# GridInverter.net
KiCad netlist of a schematic drawn in EAGLE
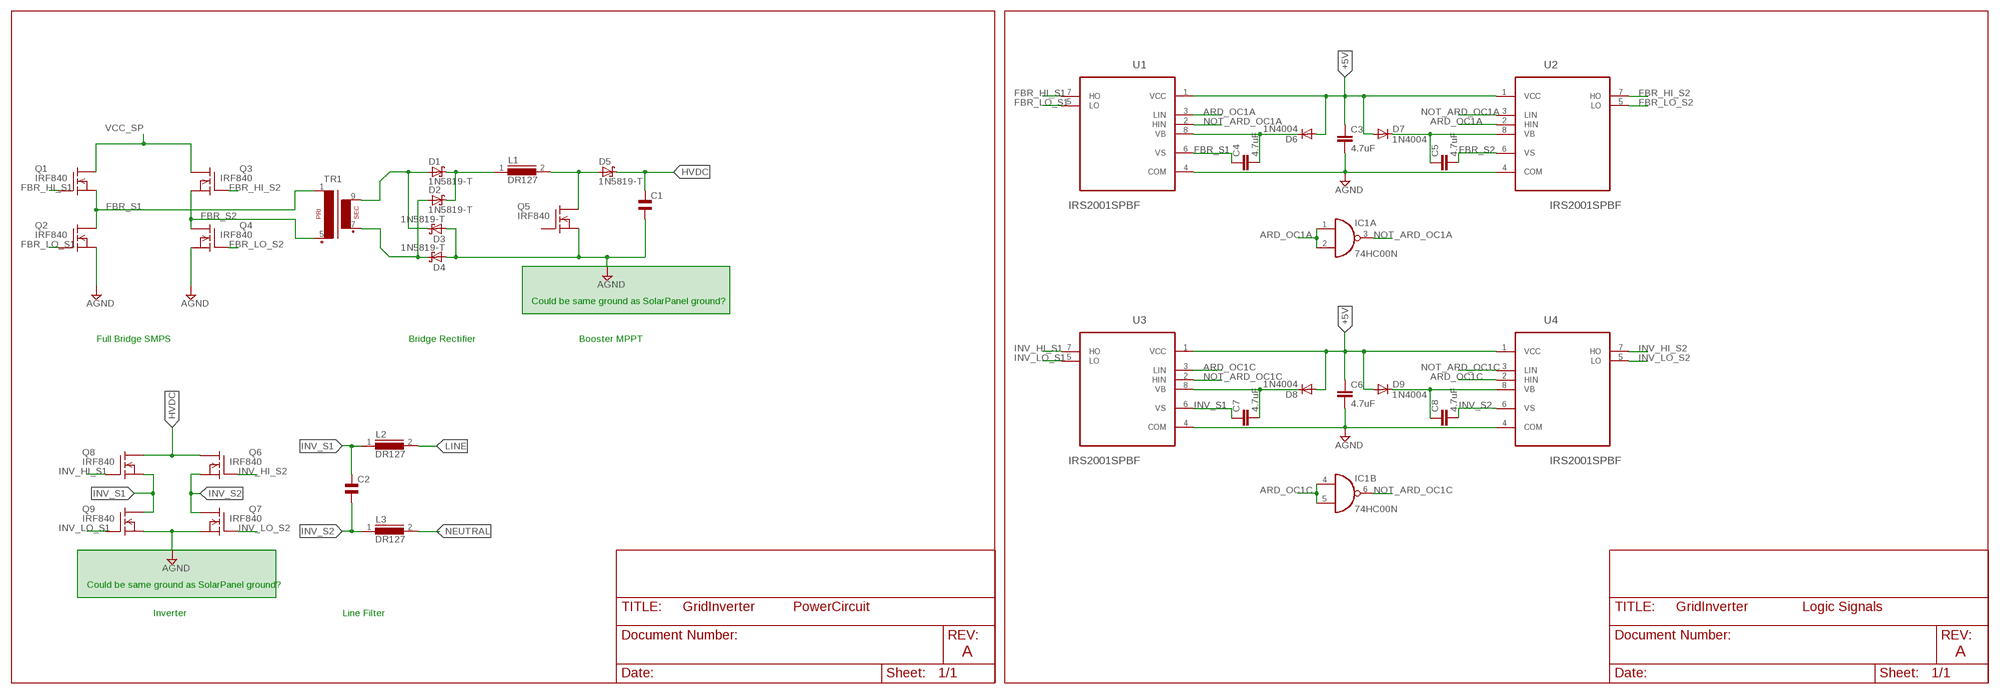
[diagram p0: schematic, sheet 1]

(export (version "E")
  (design (tool "Eeschema 10.0.6"))
  (components
    (comp (ref "C1")
      (value "EL-BI45-18AXIAL")
      (footprint "eagle-import:EU45-18")
      (libsource (lib "eagle-import") (part "EL-BI45-18AXIAL"))
    )
    (comp (ref "C2")
      (value "EL-BI45-18AXIAL")
      (footprint "eagle-import:EU45-18")
      (libsource (lib "eagle-import") (part "EL-BI45-18AXIAL"))
    )
    (comp (ref "C3")
      (value "4.7uF")
      (footprint "eagle-import:1206-CAP")
      (libsource (lib "eagle-import") (part "4.7UF-16V-20%,+80%-(1206)"))
    )
    (comp (ref "C4")
      (value "4.7uF")
      (footprint "eagle-import:1206-CAP")
      (libsource (lib "eagle-import") (part "4.7UF-16V-20%,+80%-(1206)"))
    )
    (comp (ref "C5")
      (value "4.7uF")
      (footprint "eagle-import:1206-CAP")
      (libsource (lib "eagle-import") (part "4.7UF-16V-20%,+80%-(1206)"))
    )
    (comp (ref "C6")
      (value "4.7uF")
      (footprint "eagle-import:1206-CAP")
      (libsource (lib "eagle-import") (part "4.7UF-16V-20%,+80%-(1206)"))
    )
    (comp (ref "C7")
      (value "4.7uF")
      (footprint "eagle-import:1206-CAP")
      (libsource (lib "eagle-import") (part "4.7UF-16V-20%,+80%-(1206)"))
    )
    (comp (ref "C8")
      (value "4.7uF")
      (footprint "eagle-import:1206-CAP")
      (libsource (lib "eagle-import") (part "4.7UF-16V-20%,+80%-(1206)"))
    )
    (comp (ref "D1")
      (value "1N5819-T")
      (footprint "eagle-import:DO41-7.6")
      (libsource (lib "eagle-import") (part "1N5819-T"))
    )
    (comp (ref "D2")
      (value "1N5819-T")
      (footprint "eagle-import:DO41-7.6")
      (libsource (lib "eagle-import") (part "1N5819-T"))
    )
    (comp (ref "D3")
      (value "1N5819-T")
      (footprint "eagle-import:DO41-7.6")
      (libsource (lib "eagle-import") (part "1N5819-T"))
    )
    (comp (ref "D4")
      (value "1N5819-T")
      (footprint "eagle-import:DO41-7.6")
      (libsource (lib "eagle-import") (part "1N5819-T"))
    )
    (comp (ref "D5")
      (value "1N5819-T")
      (footprint "eagle-import:DO41-7.6")
      (libsource (lib "eagle-import") (part "1N5819-T"))
    )
    (comp (ref "D6")
      (value "1N4004")
      (footprint "eagle-import:DO41-10")
      (libsource (lib "eagle-import") (part "1N4004"))
    )
    (comp (ref "D7")
      (value "1N4004")
      (footprint "eagle-import:DO41-10")
      (libsource (lib "eagle-import") (part "1N4004"))
    )
    (comp (ref "D8")
      (value "1N4004")
      (footprint "eagle-import:DO41-10")
      (libsource (lib "eagle-import") (part "1N4004"))
    )
    (comp (ref "D9")
      (value "1N4004")
      (footprint "eagle-import:DO41-10")
      (libsource (lib "eagle-import") (part "1N4004"))
    )
    (comp (ref "IC1")
      (value "74HC00N")
      (footprint "eagle-import:DIL14")
      (libsource (lib "eagle-import") (part "7400NHC"))
    )
    (comp (ref "L1")
      (value "DR127")
      (footprint "eagle-import:DR127")
      (libsource (lib "eagle-import") (part "DR127"))
    )
    (comp (ref "L2")
      (value "DR127")
      (footprint "eagle-import:DR127")
      (libsource (lib "eagle-import") (part "DR127"))
    )
    (comp (ref "L3")
      (value "DR127")
      (footprint "eagle-import:DR127")
      (libsource (lib "eagle-import") (part "DR127"))
    )
    (comp (ref "Q1")
      (value "IRF840")
      (footprint "eagle-import:TO220")
      (libsource (lib "eagle-import") (part "IRF840"))
    )
    (comp (ref "Q2")
      (value "IRF840")
      (footprint "eagle-import:TO220")
      (libsource (lib "eagle-import") (part "IRF840"))
    )
    (comp (ref "Q3")
      (value "IRF840")
      (footprint "eagle-import:TO220")
      (libsource (lib "eagle-import") (part "IRF840"))
    )
    (comp (ref "Q4")
      (value "IRF840")
      (footprint "eagle-import:TO220")
      (libsource (lib "eagle-import") (part "IRF840"))
    )
    (comp (ref "Q5")
      (value "IRF840")
      (footprint "eagle-import:TO220")
      (libsource (lib "eagle-import") (part "IRF840"))
    )
    (comp (ref "Q6")
      (value "IRF840")
      (footprint "eagle-import:TO220")
      (libsource (lib "eagle-import") (part "IRF840"))
    )
    (comp (ref "Q7")
      (value "IRF840")
      (footprint "eagle-import:TO220")
      (libsource (lib "eagle-import") (part "IRF840"))
    )
    (comp (ref "Q8")
      (value "IRF840")
      (footprint "eagle-import:TO220")
      (libsource (lib "eagle-import") (part "IRF840"))
    )
    (comp (ref "Q9")
      (value "IRF840")
      (footprint "eagle-import:TO220")
      (libsource (lib "eagle-import") (part "IRF840"))
    )
    (comp (ref "TR1")
      (value "VR11")
      (footprint "eagle-import:VR11")
      (libsource (lib "eagle-import") (part "VR11"))
    )
    (comp (ref "U1")
      (value "IRS2001SPBF")
      (footprint "eagle-import:SOIC127P600X175-8N")
      (libsource (lib "eagle-import") (part "IRS2001SPBF"))
    )
    (comp (ref "U2")
      (value "IRS2001SPBF")
      (footprint "eagle-import:SOIC127P600X175-8N")
      (libsource (lib "eagle-import") (part "IRS2001SPBF"))
    )
    (comp (ref "U3")
      (value "IRS2001SPBF")
      (footprint "eagle-import:SOIC127P600X175-8N")
      (libsource (lib "eagle-import") (part "IRS2001SPBF"))
    )
    (comp (ref "U4")
      (value "IRS2001SPBF")
      (footprint "eagle-import:SOIC127P600X175-8N")
      (libsource (lib "eagle-import") (part "IRS2001SPBF"))
    )
  )
  (nets
    (net (code "1") (name "+5V") (class "Default")
      (node (ref "C3") (pin "1") (pinfunction "1_1") (pintype "passive"))
      (node (ref "C6") (pin "1") (pinfunction "1_1") (pintype "passive"))
      (node (ref "D6") (pin "A") (pinfunction "A_A") (pintype "passive"))
      (node (ref "D7") (pin "A") (pinfunction "A_A") (pintype "passive"))
      (node (ref "D8") (pin "A") (pinfunction "A_A") (pintype "passive"))
      (node (ref "D9") (pin "A") (pinfunction "A_A") (pintype "passive"))
      (node (ref "U1") (pin "1") (pinfunction "VCC_1") (pintype "power_in"))
      (node (ref "U2") (pin "1") (pinfunction "VCC_1") (pintype "power_in"))
      (node (ref "U3") (pin "1") (pinfunction "VCC_1") (pintype "power_in"))
      (node (ref "U4") (pin "1") (pinfunction "VCC_1") (pintype "power_in"))
    )
    (net (code "2") (name "/ARD_OC1A") (class "Default")
      (node (ref "IC1") (pin "1") (pinfunction "I0_1") (pintype "input"))
      (node (ref "IC1") (pin "2") (pinfunction "I1_2") (pintype "input"))
      (node (ref "U1") (pin "3") (pinfunction "LIN_3") (pintype "input"))
      (node (ref "U2") (pin "2") (pinfunction "HIN_2") (pintype "input"))
    )
    (net (code "3") (name "/ARD_OC1C") (class "Default")
      (node (ref "IC1") (pin "4") (pinfunction "I0_4") (pintype "input"))
      (node (ref "IC1") (pin "5") (pinfunction "I1_5") (pintype "input"))
      (node (ref "U3") (pin "3") (pinfunction "LIN_3") (pintype "input"))
      (node (ref "U4") (pin "2") (pinfunction "HIN_2") (pintype "input"))
    )
    (net (code "4") (name "/FBR_HI_S1") (class "Default")
      (node (ref "Q1") (pin "1") (pinfunction "G_1") (pintype "passive"))
      (node (ref "U1") (pin "7") (pinfunction "HO_7") (pintype "output"))
    )
    (net (code "5") (name "/FBR_HI_S2") (class "Default")
      (node (ref "Q3") (pin "1") (pinfunction "G_1") (pintype "passive"))
      (node (ref "U2") (pin "7") (pinfunction "HO_7") (pintype "output"))
    )
    (net (code "6") (name "/FBR_LO_S1") (class "Default")
      (node (ref "Q2") (pin "1") (pinfunction "G_1") (pintype "passive"))
      (node (ref "U1") (pin "5") (pinfunction "LO_5") (pintype "output"))
    )
    (net (code "7") (name "/FBR_LO_S2") (class "Default")
      (node (ref "Q4") (pin "1") (pinfunction "G_1") (pintype "passive"))
      (node (ref "U2") (pin "5") (pinfunction "LO_5") (pintype "output"))
    )
    (net (code "8") (name "/FBR_S1") (class "Default")
      (node (ref "C4") (pin "1") (pinfunction "1_1") (pintype "passive"))
      (node (ref "Q1") (pin "3") (pinfunction "S_3") (pintype "passive"))
      (node (ref "Q2") (pin "2") (pinfunction "D_2") (pintype "passive"))
      (node (ref "TR1") (pin "1") (pinfunction "P1_1") (pintype "passive"))
      (node (ref "U1") (pin "6") (pinfunction "VS_6") (pintype "power_in"))
    )
    (net (code "9") (name "/FBR_S2") (class "Default")
      (node (ref "C5") (pin "2") (pinfunction "2_2") (pintype "passive"))
      (node (ref "Q3") (pin "3") (pinfunction "S_3") (pintype "passive"))
      (node (ref "Q4") (pin "2") (pinfunction "D_2") (pintype "passive"))
      (node (ref "TR1") (pin "5") (pinfunction "P2_5") (pintype "passive"))
      (node (ref "U2") (pin "6") (pinfunction "VS_6") (pintype "power_in"))
    )
    (net (code "10") (name "/INV_HI_S1") (class "Default")
      (node (ref "Q8") (pin "1") (pinfunction "G_1") (pintype "passive"))
      (node (ref "U3") (pin "7") (pinfunction "HO_7") (pintype "output"))
    )
    (net (code "11") (name "/INV_HI_S2") (class "Default")
      (node (ref "Q6") (pin "1") (pinfunction "G_1") (pintype "passive"))
      (node (ref "U4") (pin "7") (pinfunction "HO_7") (pintype "output"))
    )
    (net (code "12") (name "/INV_LO_S1") (class "Default")
      (node (ref "Q9") (pin "1") (pinfunction "G_1") (pintype "passive"))
      (node (ref "U3") (pin "5") (pinfunction "LO_5") (pintype "output"))
    )
    (net (code "13") (name "/INV_LO_S2") (class "Default")
      (node (ref "Q7") (pin "1") (pinfunction "G_1") (pintype "passive"))
      (node (ref "U4") (pin "5") (pinfunction "LO_5") (pintype "output"))
    )
    (net (code "14") (name "/NOT_ARD_OC1A") (class "Default")
      (node (ref "IC1") (pin "3") (pinfunction "O_3") (pintype "output"))
      (node (ref "U1") (pin "2") (pinfunction "HIN_2") (pintype "input"))
      (node (ref "U2") (pin "3") (pinfunction "LIN_3") (pintype "input"))
    )
    (net (code "15") (name "/NOT_ARD_OC1C") (class "Default")
      (node (ref "IC1") (pin "6") (pinfunction "O_6") (pintype "output"))
      (node (ref "U3") (pin "2") (pinfunction "HIN_2") (pintype "input"))
      (node (ref "U4") (pin "3") (pinfunction "LIN_3") (pintype "input"))
    )
    (net (code "16") (name "/VCC_SP") (class "Default")
      (node (ref "Q1") (pin "2") (pinfunction "D_2") (pintype "passive"))
      (node (ref "Q3") (pin "2") (pinfunction "D_2") (pintype "passive"))
    )
    (net (code "17") (name "AGND") (class "Default")
      (node (ref "C1") (pin "2") (pinfunction "2_2") (pintype "passive"))
      (node (ref "C3") (pin "2") (pinfunction "2_2") (pintype "passive"))
      (node (ref "C6") (pin "2") (pinfunction "2_2") (pintype "passive"))
      (node (ref "D3") (pin "A") (pinfunction "A_A") (pintype "passive"))
      (node (ref "D4") (pin "A") (pinfunction "A_A") (pintype "passive"))
      (node (ref "Q2") (pin "3") (pinfunction "S_3") (pintype "passive"))
      (node (ref "Q4") (pin "3") (pinfunction "S_3") (pintype "passive"))
      (node (ref "Q5") (pin "3") (pinfunction "S_3") (pintype "passive"))
      (node (ref "Q7") (pin "3") (pinfunction "S_3") (pintype "passive"))
      (node (ref "Q9") (pin "3") (pinfunction "S_3") (pintype "passive"))
      (node (ref "U1") (pin "4") (pinfunction "COM_4") (pintype "passive"))
      (node (ref "U2") (pin "4") (pinfunction "COM_4") (pintype "passive"))
      (node (ref "U3") (pin "4") (pinfunction "COM_4") (pintype "passive"))
      (node (ref "U4") (pin "4") (pinfunction "COM_4") (pintype "passive"))
    )
    (net (code "18") (name "HVDC") (class "Default")
      (node (ref "C1") (pin "1") (pinfunction "1_1") (pintype "passive"))
      (node (ref "D5") (pin "C") (pinfunction "C_C") (pintype "passive"))
      (node (ref "Q6") (pin "2") (pinfunction "D_2") (pintype "passive"))
      (node (ref "Q8") (pin "2") (pinfunction "D_2") (pintype "passive"))
    )
    (net (code "19") (name "INV_S1") (class "Default")
      (node (ref "C2") (pin "1") (pinfunction "1_1") (pintype "passive"))
      (node (ref "C7") (pin "1") (pinfunction "1_1") (pintype "passive"))
      (node (ref "L2") (pin "1") (pinfunction "1_1") (pintype "passive"))
      (node (ref "Q8") (pin "3") (pinfunction "S_3") (pintype "passive"))
      (node (ref "Q9") (pin "2") (pinfunction "D_2") (pintype "passive"))
      (node (ref "U3") (pin "6") (pinfunction "VS_6") (pintype "power_in"))
    )
    (net (code "20") (name "INV_S2") (class "Default")
      (node (ref "C2") (pin "2") (pinfunction "2_2") (pintype "passive"))
      (node (ref "C8") (pin "2") (pinfunction "2_2") (pintype "passive"))
      (node (ref "L3") (pin "1") (pinfunction "1_1") (pintype "passive"))
      (node (ref "Q6") (pin "3") (pinfunction "S_3") (pintype "passive"))
      (node (ref "Q7") (pin "2") (pinfunction "D_2") (pintype "passive"))
      (node (ref "U4") (pin "6") (pinfunction "VS_6") (pintype "power_in"))
    )
    (net (code "21") (name "LINE") (class "Default")
      (node (ref "L2") (pin "2") (pinfunction "2_2") (pintype "passive"))
    )
    (net (code "22") (name "NEUTRAL") (class "Default")
      (node (ref "L3") (pin "2") (pinfunction "2_2") (pintype "passive"))
    )
    (net (code "23") (name "Net-(D1-PadC)") (class "Default")
      (node (ref "D1") (pin "C") (pinfunction "C_C") (pintype "passive"))
      (node (ref "D2") (pin "C") (pinfunction "C_C") (pintype "passive"))
      (node (ref "L1") (pin "1") (pinfunction "1_1") (pintype "passive"))
    )
    (net (code "24") (name "Net-(Q5-D)") (class "Default")
      (node (ref "D5") (pin "A") (pinfunction "A_A") (pintype "passive"))
      (node (ref "L1") (pin "2") (pinfunction "2_2") (pintype "passive"))
      (node (ref "Q5") (pin "2") (pinfunction "D_2") (pintype "passive"))
    )
    (net (code "25") (name "Net-(TR1-S3)") (class "Default")
      (node (ref "D2") (pin "A") (pinfunction "A_A") (pintype "passive"))
      (node (ref "D4") (pin "C") (pinfunction "C_C") (pintype "passive"))
      (node (ref "TR1") (pin "7") (pinfunction "S3_7") (pintype "passive"))
    )
    (net (code "26") (name "Net-(TR1-S4)") (class "Default")
      (node (ref "D1") (pin "A") (pinfunction "A_A") (pintype "passive"))
      (node (ref "D3") (pin "C") (pinfunction "C_C") (pintype "passive"))
      (node (ref "TR1") (pin "9") (pinfunction "S4_9") (pintype "passive"))
    )
    (net (code "27") (name "Net-(U1-VB)") (class "Default")
      (node (ref "C4") (pin "2") (pinfunction "2_2") (pintype "passive"))
      (node (ref "D6") (pin "C") (pinfunction "C_C") (pintype "passive"))
      (node (ref "U1") (pin "8") (pinfunction "VB_8") (pintype "input"))
    )
    (net (code "28") (name "Net-(U2-VB)") (class "Default")
      (node (ref "C5") (pin "1") (pinfunction "1_1") (pintype "passive"))
      (node (ref "D7") (pin "C") (pinfunction "C_C") (pintype "passive"))
      (node (ref "U2") (pin "8") (pinfunction "VB_8") (pintype "input"))
    )
    (net (code "29") (name "Net-(U3-VB)") (class "Default")
      (node (ref "C7") (pin "2") (pinfunction "2_2") (pintype "passive"))
      (node (ref "D8") (pin "C") (pinfunction "C_C") (pintype "passive"))
      (node (ref "U3") (pin "8") (pinfunction "VB_8") (pintype "input"))
    )
    (net (code "30") (name "Net-(U4-VB)") (class "Default")
      (node (ref "C8") (pin "1") (pinfunction "1_1") (pintype "passive"))
      (node (ref "D9") (pin "C") (pinfunction "C_C") (pintype "passive"))
      (node (ref "U4") (pin "8") (pinfunction "VB_8") (pintype "input"))
    )
    (net (code "31") (name "unconnected-(Q5-G-Pad1)") (class "Default")
      (node (ref "Q5") (pin "1") (pinfunction "G_1") (pintype "passive"))
    )
  )
)
